# Dongle.net
KiCad netlist of a schematic drawn in Altium Designer
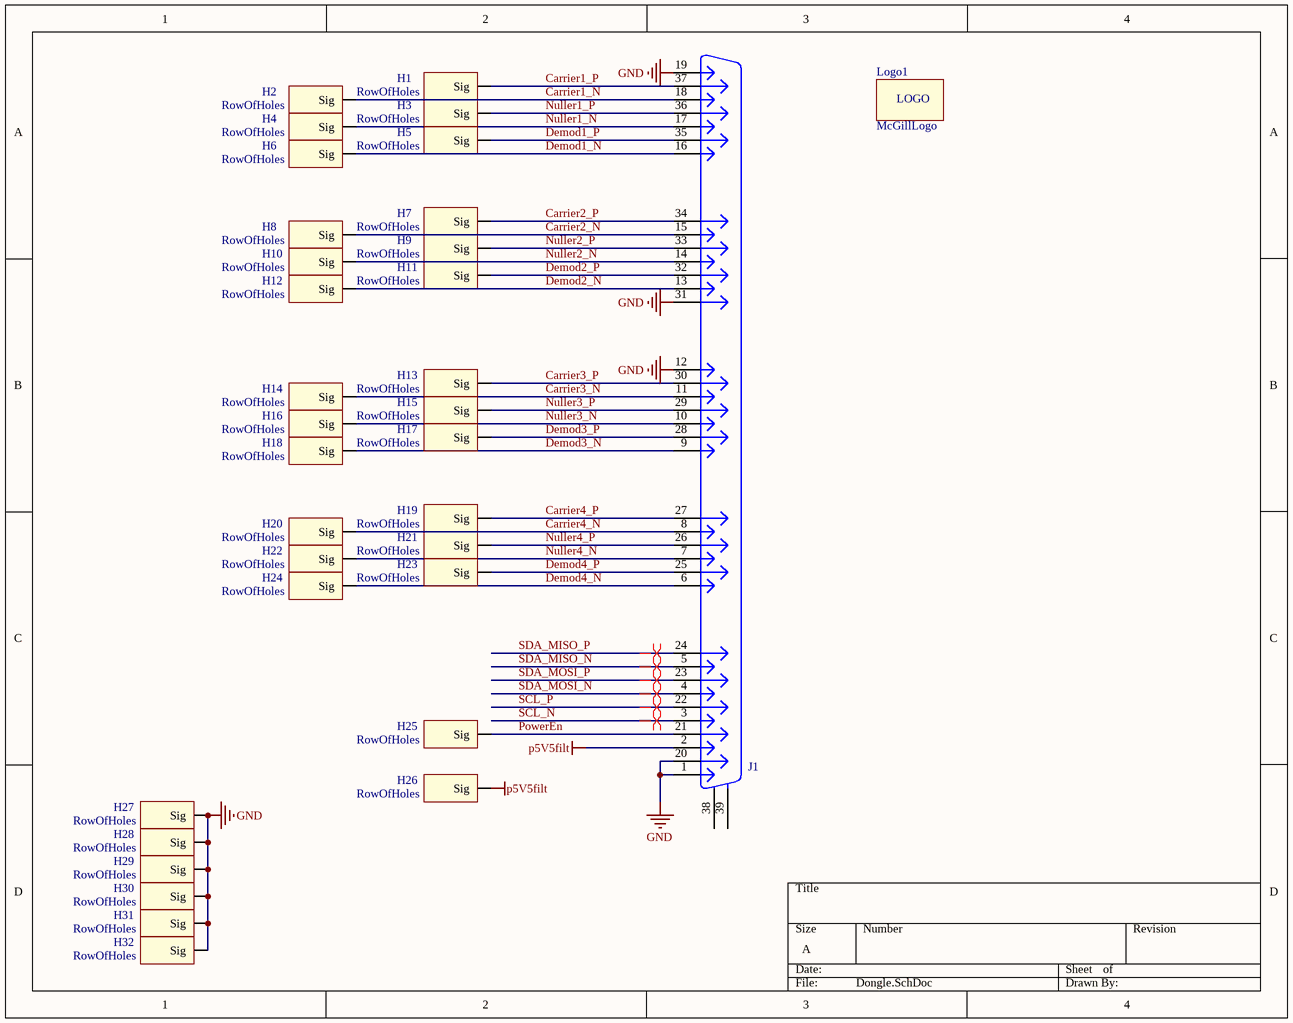
[diagram p0: Dongle.SchDoc]

(export (version "E")
  (design (tool "Eeschema 10.0.6"))
  (components
    (comp (ref "H1")
      (value "RowOfHoles")
      (footprint "RowOfHoles")
      (libsource (lib "MGMEZZ04_Loopback") (part "RowOfHoles"))
    )
    (comp (ref "H2")
      (value "RowOfHoles")
      (footprint "RowOfHoles")
      (libsource (lib "MGMEZZ04_Loopback") (part "RowOfHoles"))
    )
    (comp (ref "H3")
      (value "RowOfHoles")
      (footprint "RowOfHoles")
      (libsource (lib "MGMEZZ04_Loopback") (part "RowOfHoles"))
    )
    (comp (ref "H4")
      (value "RowOfHoles")
      (footprint "RowOfHoles")
      (libsource (lib "MGMEZZ04_Loopback") (part "RowOfHoles"))
    )
    (comp (ref "H5")
      (value "RowOfHoles")
      (footprint "RowOfHoles")
      (libsource (lib "MGMEZZ04_Loopback") (part "RowOfHoles"))
    )
    (comp (ref "H6")
      (value "RowOfHoles")
      (footprint "RowOfHoles")
      (libsource (lib "MGMEZZ04_Loopback") (part "RowOfHoles"))
    )
    (comp (ref "H7")
      (value "RowOfHoles")
      (footprint "RowOfHoles")
      (libsource (lib "MGMEZZ04_Loopback") (part "RowOfHoles"))
    )
    (comp (ref "H8")
      (value "RowOfHoles")
      (footprint "RowOfHoles")
      (libsource (lib "MGMEZZ04_Loopback") (part "RowOfHoles"))
    )
    (comp (ref "H9")
      (value "RowOfHoles")
      (footprint "RowOfHoles")
      (libsource (lib "MGMEZZ04_Loopback") (part "RowOfHoles"))
    )
    (comp (ref "H10")
      (value "RowOfHoles")
      (footprint "RowOfHoles")
      (libsource (lib "MGMEZZ04_Loopback") (part "RowOfHoles"))
    )
    (comp (ref "H11")
      (value "RowOfHoles")
      (footprint "RowOfHoles")
      (libsource (lib "MGMEZZ04_Loopback") (part "RowOfHoles"))
    )
    (comp (ref "H12")
      (value "RowOfHoles")
      (footprint "RowOfHoles")
      (libsource (lib "MGMEZZ04_Loopback") (part "RowOfHoles"))
    )
    (comp (ref "H13")
      (value "RowOfHoles")
      (footprint "RowOfHoles")
      (libsource (lib "MGMEZZ04_Loopback") (part "RowOfHoles"))
    )
    (comp (ref "H14")
      (value "RowOfHoles")
      (footprint "RowOfHoles")
      (libsource (lib "MGMEZZ04_Loopback") (part "RowOfHoles"))
    )
    (comp (ref "H15")
      (value "RowOfHoles")
      (footprint "RowOfHoles")
      (libsource (lib "MGMEZZ04_Loopback") (part "RowOfHoles"))
    )
    (comp (ref "H16")
      (value "RowOfHoles")
      (footprint "RowOfHoles")
      (libsource (lib "MGMEZZ04_Loopback") (part "RowOfHoles"))
    )
    (comp (ref "H17")
      (value "RowOfHoles")
      (footprint "RowOfHoles")
      (libsource (lib "MGMEZZ04_Loopback") (part "RowOfHoles"))
    )
    (comp (ref "H18")
      (value "RowOfHoles")
      (footprint "RowOfHoles")
      (libsource (lib "MGMEZZ04_Loopback") (part "RowOfHoles"))
    )
    (comp (ref "H19")
      (value "RowOfHoles")
      (footprint "RowOfHoles")
      (libsource (lib "MGMEZZ04_Loopback") (part "RowOfHoles"))
    )
    (comp (ref "H20")
      (value "RowOfHoles")
      (footprint "RowOfHoles")
      (libsource (lib "MGMEZZ04_Loopback") (part "RowOfHoles"))
    )
    (comp (ref "H21")
      (value "RowOfHoles")
      (footprint "RowOfHoles")
      (libsource (lib "MGMEZZ04_Loopback") (part "RowOfHoles"))
    )
    (comp (ref "H22")
      (value "RowOfHoles")
      (footprint "RowOfHoles")
      (libsource (lib "MGMEZZ04_Loopback") (part "RowOfHoles"))
    )
    (comp (ref "H23")
      (value "RowOfHoles")
      (footprint "RowOfHoles")
      (libsource (lib "MGMEZZ04_Loopback") (part "RowOfHoles"))
    )
    (comp (ref "H24")
      (value "RowOfHoles")
      (footprint "RowOfHoles")
      (libsource (lib "MGMEZZ04_Loopback") (part "RowOfHoles"))
    )
    (comp (ref "H25")
      (value "RowOfHoles")
      (footprint "RowOfHoles")
      (libsource (lib "MGMEZZ04_Loopback") (part "RowOfHoles"))
    )
    (comp (ref "H26")
      (value "RowOfHoles")
      (footprint "RowOfHoles")
      (libsource (lib "MGMEZZ04_Loopback") (part "RowOfHoles"))
    )
    (comp (ref "H27")
      (value "RowOfHoles")
      (footprint "RowOfHoles")
      (libsource (lib "MGMEZZ04_Loopback") (part "RowOfHoles"))
    )
    (comp (ref "H28")
      (value "RowOfHoles")
      (footprint "RowOfHoles")
      (libsource (lib "MGMEZZ04_Loopback") (part "RowOfHoles"))
    )
    (comp (ref "H29")
      (value "RowOfHoles")
      (footprint "RowOfHoles")
      (libsource (lib "MGMEZZ04_Loopback") (part "RowOfHoles"))
    )
    (comp (ref "H30")
      (value "RowOfHoles")
      (footprint "RowOfHoles")
      (libsource (lib "MGMEZZ04_Loopback") (part "RowOfHoles"))
    )
    (comp (ref "H31")
      (value "RowOfHoles")
      (footprint "RowOfHoles")
      (libsource (lib "MGMEZZ04_Loopback") (part "RowOfHoles"))
    )
    (comp (ref "H32")
      (value "RowOfHoles")
      (footprint "RowOfHoles")
      (libsource (lib "MGMEZZ04_Loopback") (part "RowOfHoles"))
    )
    (comp (ref "J1")
      (value "DB37M")
      (footprint "DSUB37-M")
      (fields
        (field (name "MANUFACTURER") "Norcomp")
        (field (name "MANUFACTURER PART NUMBER") "182-037-113R531")
      )
      (libsource (lib "MGMEZZ04_Loopback") (part "DB37M"))
    )
    (comp (ref "Logo1")
      (value "McGillLogo")
      (footprint "McGillLogo1")
      (description "Silkscreen Logo")
      (fields (field (name "MANUFACTURER") "McGill"))
      (libsource (lib "MGMEZZ04_Loopback") (part "Logo"))
    )
  )
  (nets
    (net (code "1") (name "/Carrier1_N") (class "Default")
      (node (ref "H2") (pin "0") (pinfunction "Sig_0") (pintype "passive"))
      (node (ref "J1") (pin "18") (pinfunction "18_18") (pintype "passive"))
    )
    (net (code "2") (name "/Carrier1_P") (class "Default")
      (node (ref "H1") (pin "0") (pinfunction "Sig_0") (pintype "passive"))
      (node (ref "J1") (pin "37") (pinfunction "37_37") (pintype "passive"))
    )
    (net (code "3") (name "/Carrier2_N") (class "Default")
      (node (ref "H8") (pin "0") (pinfunction "Sig_0") (pintype "passive"))
      (node (ref "J1") (pin "15") (pinfunction "15_15") (pintype "passive"))
    )
    (net (code "4") (name "/Carrier2_P") (class "Default")
      (node (ref "H7") (pin "0") (pinfunction "Sig_0") (pintype "passive"))
      (node (ref "J1") (pin "34") (pinfunction "34_34") (pintype "passive"))
    )
    (net (code "5") (name "/Carrier3_N") (class "Default")
      (node (ref "H14") (pin "0") (pinfunction "Sig_0") (pintype "passive"))
      (node (ref "J1") (pin "11") (pinfunction "11_11") (pintype "passive"))
    )
    (net (code "6") (name "/Carrier3_P") (class "Default")
      (node (ref "H13") (pin "0") (pinfunction "Sig_0") (pintype "passive"))
      (node (ref "J1") (pin "30") (pinfunction "30_30") (pintype "passive"))
    )
    (net (code "7") (name "/Carrier4_N") (class "Default")
      (node (ref "H20") (pin "0") (pinfunction "Sig_0") (pintype "passive"))
      (node (ref "J1") (pin "8") (pinfunction "8_8") (pintype "passive"))
    )
    (net (code "8") (name "/Carrier4_P") (class "Default")
      (node (ref "H19") (pin "0") (pinfunction "Sig_0") (pintype "passive"))
      (node (ref "J1") (pin "27") (pinfunction "27_27") (pintype "passive"))
    )
    (net (code "9") (name "/Demod1_N") (class "Default")
      (node (ref "H6") (pin "0") (pinfunction "Sig_0") (pintype "passive"))
      (node (ref "J1") (pin "16") (pinfunction "16_16") (pintype "passive"))
    )
    (net (code "10") (name "/Demod1_P") (class "Default")
      (node (ref "H5") (pin "0") (pinfunction "Sig_0") (pintype "passive"))
      (node (ref "J1") (pin "35") (pinfunction "35_35") (pintype "passive"))
    )
    (net (code "11") (name "/Demod2_N") (class "Default")
      (node (ref "H12") (pin "0") (pinfunction "Sig_0") (pintype "passive"))
      (node (ref "J1") (pin "13") (pinfunction "13_13") (pintype "passive"))
    )
    (net (code "12") (name "/Demod2_P") (class "Default")
      (node (ref "H11") (pin "0") (pinfunction "Sig_0") (pintype "passive"))
      (node (ref "J1") (pin "32") (pinfunction "32_32") (pintype "passive"))
    )
    (net (code "13") (name "/Demod3_N") (class "Default")
      (node (ref "H18") (pin "0") (pinfunction "Sig_0") (pintype "passive"))
      (node (ref "J1") (pin "9") (pinfunction "9_9") (pintype "passive"))
    )
    (net (code "14") (name "/Demod3_P") (class "Default")
      (node (ref "H17") (pin "0") (pinfunction "Sig_0") (pintype "passive"))
      (node (ref "J1") (pin "28") (pinfunction "28_28") (pintype "passive"))
    )
    (net (code "15") (name "/Demod4_N") (class "Default")
      (node (ref "H24") (pin "0") (pinfunction "Sig_0") (pintype "passive"))
      (node (ref "J1") (pin "6") (pinfunction "6_6") (pintype "passive"))
    )
    (net (code "16") (name "/Demod4_P") (class "Default")
      (node (ref "H23") (pin "0") (pinfunction "Sig_0") (pintype "passive"))
      (node (ref "J1") (pin "25") (pinfunction "25_25") (pintype "passive"))
    )
    (net (code "17") (name "/Nuller1_N") (class "Default")
      (node (ref "H4") (pin "0") (pinfunction "Sig_0") (pintype "passive"))
      (node (ref "J1") (pin "17") (pinfunction "17_17") (pintype "passive"))
    )
    (net (code "18") (name "/Nuller1_P") (class "Default")
      (node (ref "H3") (pin "0") (pinfunction "Sig_0") (pintype "passive"))
      (node (ref "J1") (pin "36") (pinfunction "36_36") (pintype "passive"))
    )
    (net (code "19") (name "/Nuller2_N") (class "Default")
      (node (ref "H10") (pin "0") (pinfunction "Sig_0") (pintype "passive"))
      (node (ref "J1") (pin "14") (pinfunction "14_14") (pintype "passive"))
    )
    (net (code "20") (name "/Nuller2_P") (class "Default")
      (node (ref "H9") (pin "0") (pinfunction "Sig_0") (pintype "passive"))
      (node (ref "J1") (pin "33") (pinfunction "33_33") (pintype "passive"))
    )
    (net (code "21") (name "/Nuller3_N") (class "Default")
      (node (ref "H16") (pin "0") (pinfunction "Sig_0") (pintype "passive"))
      (node (ref "J1") (pin "10") (pinfunction "10_10") (pintype "passive"))
    )
    (net (code "22") (name "/Nuller3_P") (class "Default")
      (node (ref "H15") (pin "0") (pinfunction "Sig_0") (pintype "passive"))
      (node (ref "J1") (pin "29") (pinfunction "29_29") (pintype "passive"))
    )
    (net (code "23") (name "/Nuller4_N") (class "Default")
      (node (ref "H22") (pin "0") (pinfunction "Sig_0") (pintype "passive"))
      (node (ref "J1") (pin "7") (pinfunction "7_7") (pintype "passive"))
    )
    (net (code "24") (name "/Nuller4_P") (class "Default")
      (node (ref "H21") (pin "0") (pinfunction "Sig_0") (pintype "passive"))
      (node (ref "J1") (pin "26") (pinfunction "26_26") (pintype "passive"))
    )
    (net (code "25") (name "/PowerEn") (class "Default")
      (node (ref "H25") (pin "0") (pinfunction "Sig_0") (pintype "passive"))
      (node (ref "J1") (pin "21") (pinfunction "21_21") (pintype "passive"))
    )
    (net (code "26") (name "/SCL_N") (class "Default")
      (node (ref "J1") (pin "3") (pinfunction "3_3") (pintype "passive"))
    )
    (net (code "27") (name "/SCL_P") (class "Default")
      (node (ref "J1") (pin "22") (pinfunction "22_22") (pintype "passive"))
    )
    (net (code "28") (name "/SDA_MISO_N") (class "Default")
      (node (ref "J1") (pin "5") (pinfunction "5_5") (pintype "passive"))
    )
    (net (code "29") (name "/SDA_MISO_P") (class "Default")
      (node (ref "J1") (pin "24") (pinfunction "24_24") (pintype "passive"))
    )
    (net (code "30") (name "/SDA_MOSI_N") (class "Default")
      (node (ref "J1") (pin "4") (pinfunction "4_4") (pintype "passive"))
    )
    (net (code "31") (name "/SDA_MOSI_P") (class "Default")
      (node (ref "J1") (pin "23") (pinfunction "23_23") (pintype "passive"))
    )
    (net (code "32") (name "GND") (class "Default")
      (node (ref "H27") (pin "0") (pinfunction "Sig_0") (pintype "passive"))
      (node (ref "H28") (pin "0") (pinfunction "Sig_0") (pintype "passive"))
      (node (ref "H29") (pin "0") (pinfunction "Sig_0") (pintype "passive"))
      (node (ref "H30") (pin "0") (pinfunction "Sig_0") (pintype "passive"))
      (node (ref "H31") (pin "0") (pinfunction "Sig_0") (pintype "passive"))
      (node (ref "H32") (pin "0") (pinfunction "Sig_0") (pintype "passive"))
      (node (ref "J1") (pin "1") (pinfunction "1_1") (pintype "passive"))
      (node (ref "J1") (pin "12") (pinfunction "12_12") (pintype "passive"))
      (node (ref "J1") (pin "19") (pinfunction "19_19") (pintype "passive"))
      (node (ref "J1") (pin "20") (pinfunction "20_20") (pintype "passive"))
      (node (ref "J1") (pin "31") (pinfunction "31_31") (pintype "passive"))
    )
    (net (code "33") (name "p5V5filt") (class "Default")
      (node (ref "H26") (pin "0") (pinfunction "Sig_0") (pintype "passive"))
      (node (ref "J1") (pin "2") (pinfunction "2_2") (pintype "passive"))
    )
    (net (code "34") (name "unconnected-(J1-MH1-Pad38)") (class "Default")
      (node (ref "J1") (pin "38") (pinfunction "MH1_38") (pintype "passive"))
    )
    (net (code "35") (name "unconnected-(J1-MH2-Pad39)") (class "Default")
      (node (ref "J1") (pin "39") (pinfunction "MH2_39") (pintype "passive"))
    )
  )
)
